# flash-pgm.net
KiCad netlist of a schematic drawn in EAGLE
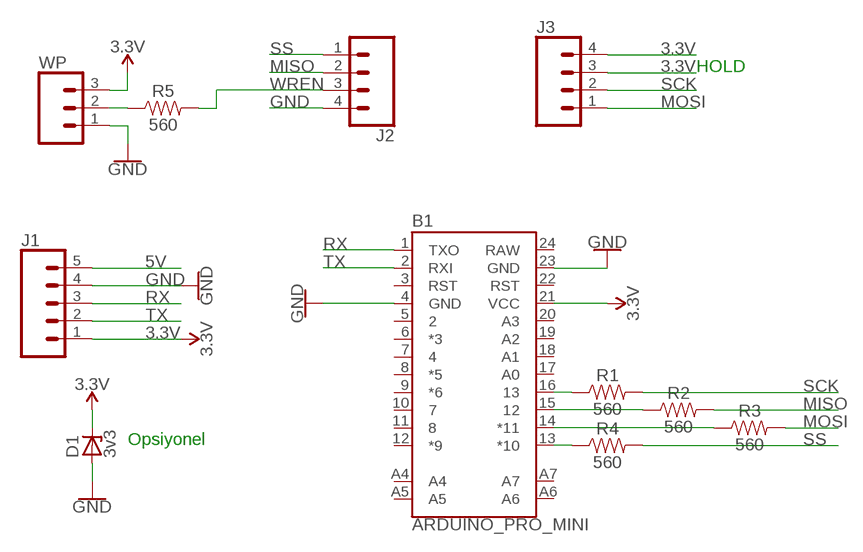
[diagram p0: schematic, sheet 1]

(export (version "E")
  (design (tool "Eeschema 10.0.6"))
  (components
    (comp (ref "B1")
      (value "ARDUINO_PRO_MINI")
      (footprint "eagle-import:ARDUINO_PRO_MINI")
      (libsource (lib "eagle-import") (part "ARDUINO_PRO_MINI"))
    )
    (comp (ref "D1")
      (value "3v3")
      (footprint "eagle-import:C1702-15")
      (libsource (lib "eagle-import") (part "ZENER-DIODEC1702-15"))
    )
    (comp (ref "J1")
      (value "CONN_05")
      (footprint "eagle-import:1X05")
      (libsource (lib "eagle-import") (part "CONN_05"))
    )
    (comp (ref "J2")
      (value "CONN_04")
      (footprint "eagle-import:1X04")
      (libsource (lib "eagle-import") (part "CONN_04"))
    )
    (comp (ref "J3")
      (value "CONN_04")
      (footprint "eagle-import:1X04")
      (libsource (lib "eagle-import") (part "CONN_04"))
    )
    (comp (ref "R1")
      (value "560")
      (footprint "eagle-import:AXIAL-0.3")
      (libsource (lib "eagle-import") (part "RESISTORAXIAL-0.3"))
    )
    (comp (ref "R2")
      (value "560")
      (footprint "eagle-import:AXIAL-0.3")
      (libsource (lib "eagle-import") (part "RESISTORAXIAL-0.3"))
    )
    (comp (ref "R3")
      (value "560")
      (footprint "eagle-import:AXIAL-0.3")
      (libsource (lib "eagle-import") (part "RESISTORAXIAL-0.3"))
    )
    (comp (ref "R4")
      (value "560")
      (footprint "eagle-import:AXIAL-0.3")
      (libsource (lib "eagle-import") (part "RESISTORAXIAL-0.3"))
    )
    (comp (ref "R5")
      (value "560")
      (footprint "eagle-import:AXIAL-0.3")
      (libsource (lib "eagle-import") (part "RESISTORAXIAL-0.3"))
    )
    (comp (ref "WP")
      (value "CONN_03")
      (footprint "eagle-import:1X03")
      (libsource (lib "eagle-import") (part "CONN_03"))
    )
  )
  (nets
    (net (code "1") (name "/5V") (class "Default")
      (node (ref "J1") (pin "5") (pinfunction "5_5") (pintype "passive"))
    )
    (net (code "2") (name "/MISO") (class "Default")
      (node (ref "J2") (pin "2") (pinfunction "2_2") (pintype "passive"))
      (node (ref "R2") (pin "P$2") (pinfunction "2_P$2") (pintype "passive"))
    )
    (net (code "3") (name "/MOSI") (class "Default")
      (node (ref "J3") (pin "1") (pinfunction "1_1") (pintype "passive"))
      (node (ref "R3") (pin "P$2") (pinfunction "2_P$2") (pintype "passive"))
    )
    (net (code "4") (name "/RAW") (class "Default")
      (node (ref "B1") (pin "24") (pinfunction "RAW_24") (pintype "power_in"))
    )
    (net (code "5") (name "/RX") (class "Default")
      (node (ref "B1") (pin "1") (pinfunction "TXO_1") (pintype "bidirectional"))
      (node (ref "J1") (pin "3") (pinfunction "3_3") (pintype "passive"))
    )
    (net (code "6") (name "/SCK") (class "Default")
      (node (ref "J3") (pin "2") (pinfunction "2_2") (pintype "passive"))
      (node (ref "R1") (pin "P$2") (pinfunction "2_P$2") (pintype "passive"))
    )
    (net (code "7") (name "/SS") (class "Default")
      (node (ref "J2") (pin "1") (pinfunction "1_1") (pintype "passive"))
      (node (ref "R4") (pin "P$2") (pinfunction "2_P$2") (pintype "passive"))
    )
    (net (code "8") (name "/TX") (class "Default")
      (node (ref "B1") (pin "2") (pinfunction "RXI_2") (pintype "bidirectional"))
      (node (ref "J1") (pin "2") (pinfunction "2_2") (pintype "passive"))
    )
    (net (code "9") (name "/WREN") (class "Default")
      (node (ref "J2") (pin "3") (pinfunction "3_3") (pintype "passive"))
      (node (ref "R5") (pin "P$2") (pinfunction "2_P$2") (pintype "passive"))
    )
    (net (code "10") (name "3.3V") (class "Default")
      (node (ref "B1") (pin "21") (pinfunction "VCC_21") (pintype "power_in"))
      (node (ref "D1") (pin "C") (pinfunction "C_C") (pintype "passive"))
      (node (ref "J1") (pin "1") (pinfunction "1_1") (pintype "passive"))
      (node (ref "J3") (pin "3") (pinfunction "3_3") (pintype "passive"))
      (node (ref "J3") (pin "4") (pinfunction "4_4") (pintype "passive"))
      (node (ref "WP") (pin "3") (pinfunction "3_3") (pintype "passive"))
    )
    (net (code "11") (name "GND") (class "Default")
      (node (ref "B1") (pin "23") (pinfunction "GND_23") (pintype "power_in"))
      (node (ref "B1") (pin "4") (pinfunction "GND_4") (pintype "power_in"))
      (node (ref "D1") (pin "A") (pinfunction "A_A") (pintype "passive"))
      (node (ref "J1") (pin "4") (pinfunction "4_4") (pintype "passive"))
      (node (ref "J2") (pin "4") (pinfunction "4_4") (pintype "passive"))
      (node (ref "WP") (pin "1") (pinfunction "1_1") (pintype "passive"))
    )
    (net (code "12") (name "Net-(B1-*10)") (class "Default")
      (node (ref "B1") (pin "13") (pinfunction "*10_13") (pintype "bidirectional"))
      (node (ref "R4") (pin "P$1") (pinfunction "1_P$1") (pintype "passive"))
    )
    (net (code "13") (name "Net-(B1-*11)") (class "Default")
      (node (ref "B1") (pin "14") (pinfunction "*11_14") (pintype "bidirectional"))
      (node (ref "R3") (pin "P$1") (pinfunction "1_P$1") (pintype "passive"))
    )
    (net (code "14") (name "Net-(B1-12)") (class "Default")
      (node (ref "B1") (pin "15") (pinfunction "12_15") (pintype "bidirectional"))
      (node (ref "R2") (pin "P$1") (pinfunction "1_P$1") (pintype "passive"))
    )
    (net (code "15") (name "Net-(B1-13)") (class "Default")
      (node (ref "B1") (pin "16") (pinfunction "13_16") (pintype "bidirectional"))
      (node (ref "R1") (pin "P$1") (pinfunction "1_P$1") (pintype "passive"))
    )
    (net (code "16") (name "Net-(R5-1)") (class "Default")
      (node (ref "R5") (pin "P$1") (pinfunction "1_P$1") (pintype "passive"))
      (node (ref "WP") (pin "2") (pinfunction "2_2") (pintype "passive"))
    )
    (net (code "17") (name "unconnected-(B1-*3-Pad6)") (class "Default")
      (node (ref "B1") (pin "6") (pinfunction "*3_6") (pintype "bidirectional"))
    )
    (net (code "18") (name "unconnected-(B1-*5-Pad8)") (class "Default")
      (node (ref "B1") (pin "8") (pinfunction "*5_8") (pintype "bidirectional"))
    )
    (net (code "19") (name "unconnected-(B1-*6-Pad9)") (class "Default")
      (node (ref "B1") (pin "9") (pinfunction "*6_9") (pintype "bidirectional"))
    )
    (net (code "20") (name "unconnected-(B1-*9-Pad12)") (class "Default")
      (node (ref "B1") (pin "12") (pinfunction "*9_12") (pintype "bidirectional"))
    )
    (net (code "21") (name "unconnected-(B1-2-Pad5)") (class "Default")
      (node (ref "B1") (pin "5") (pinfunction "2_5") (pintype "bidirectional"))
    )
    (net (code "22") (name "unconnected-(B1-4-Pad7)") (class "Default")
      (node (ref "B1") (pin "7") (pinfunction "4_7") (pintype "bidirectional"))
    )
    (net (code "23") (name "unconnected-(B1-7-Pad10)") (class "Default")
      (node (ref "B1") (pin "10") (pinfunction "7_10") (pintype "bidirectional"))
    )
    (net (code "24") (name "unconnected-(B1-8-Pad11)") (class "Default")
      (node (ref "B1") (pin "11") (pinfunction "8_11") (pintype "bidirectional"))
    )
    (net (code "25") (name "unconnected-(B1-A0-Pad17)") (class "Default")
      (node (ref "B1") (pin "17") (pinfunction "A0_17") (pintype "bidirectional"))
    )
    (net (code "26") (name "unconnected-(B1-A1-Pad18)") (class "Default")
      (node (ref "B1") (pin "18") (pinfunction "A1_18") (pintype "bidirectional"))
    )
    (net (code "27") (name "unconnected-(B1-A2-Pad19)") (class "Default")
      (node (ref "B1") (pin "19") (pinfunction "A2_19") (pintype "bidirectional"))
    )
    (net (code "28") (name "unconnected-(B1-A3-Pad20)") (class "Default")
      (node (ref "B1") (pin "20") (pinfunction "A3_20") (pintype "bidirectional"))
    )
    (net (code "29") (name "unconnected-(B1-PadA4)") (class "Default")
      (node (ref "B1") (pin "A4") (pinfunction "A4_A4") (pintype "bidirectional"))
    )
    (net (code "30") (name "unconnected-(B1-PadA5)") (class "Default")
      (node (ref "B1") (pin "A5") (pinfunction "A5_A5") (pintype "bidirectional"))
    )
    (net (code "31") (name "unconnected-(B1-PadA6)") (class "Default")
      (node (ref "B1") (pin "A6") (pinfunction "A6_A6") (pintype "bidirectional"))
    )
    (net (code "32") (name "unconnected-(B1-PadA7)") (class "Default")
      (node (ref "B1") (pin "A7") (pinfunction "A7_A7") (pintype "bidirectional"))
    )
    (net (code "33") (name "unconnected-(B1-RST-Pad3)") (class "Default")
      (node (ref "B1") (pin "3") (pinfunction "RST_3") (pintype "bidirectional"))
    )
    (net (code "34") (name "unconnected-(B1-RST-Pad22)") (class "Default")
      (node (ref "B1") (pin "22") (pinfunction "RST_22") (pintype "bidirectional"))
    )
  )
)
